# doodle_with_clock3_jump3.net
KiCad netlist of a schematic drawn in EAGLE
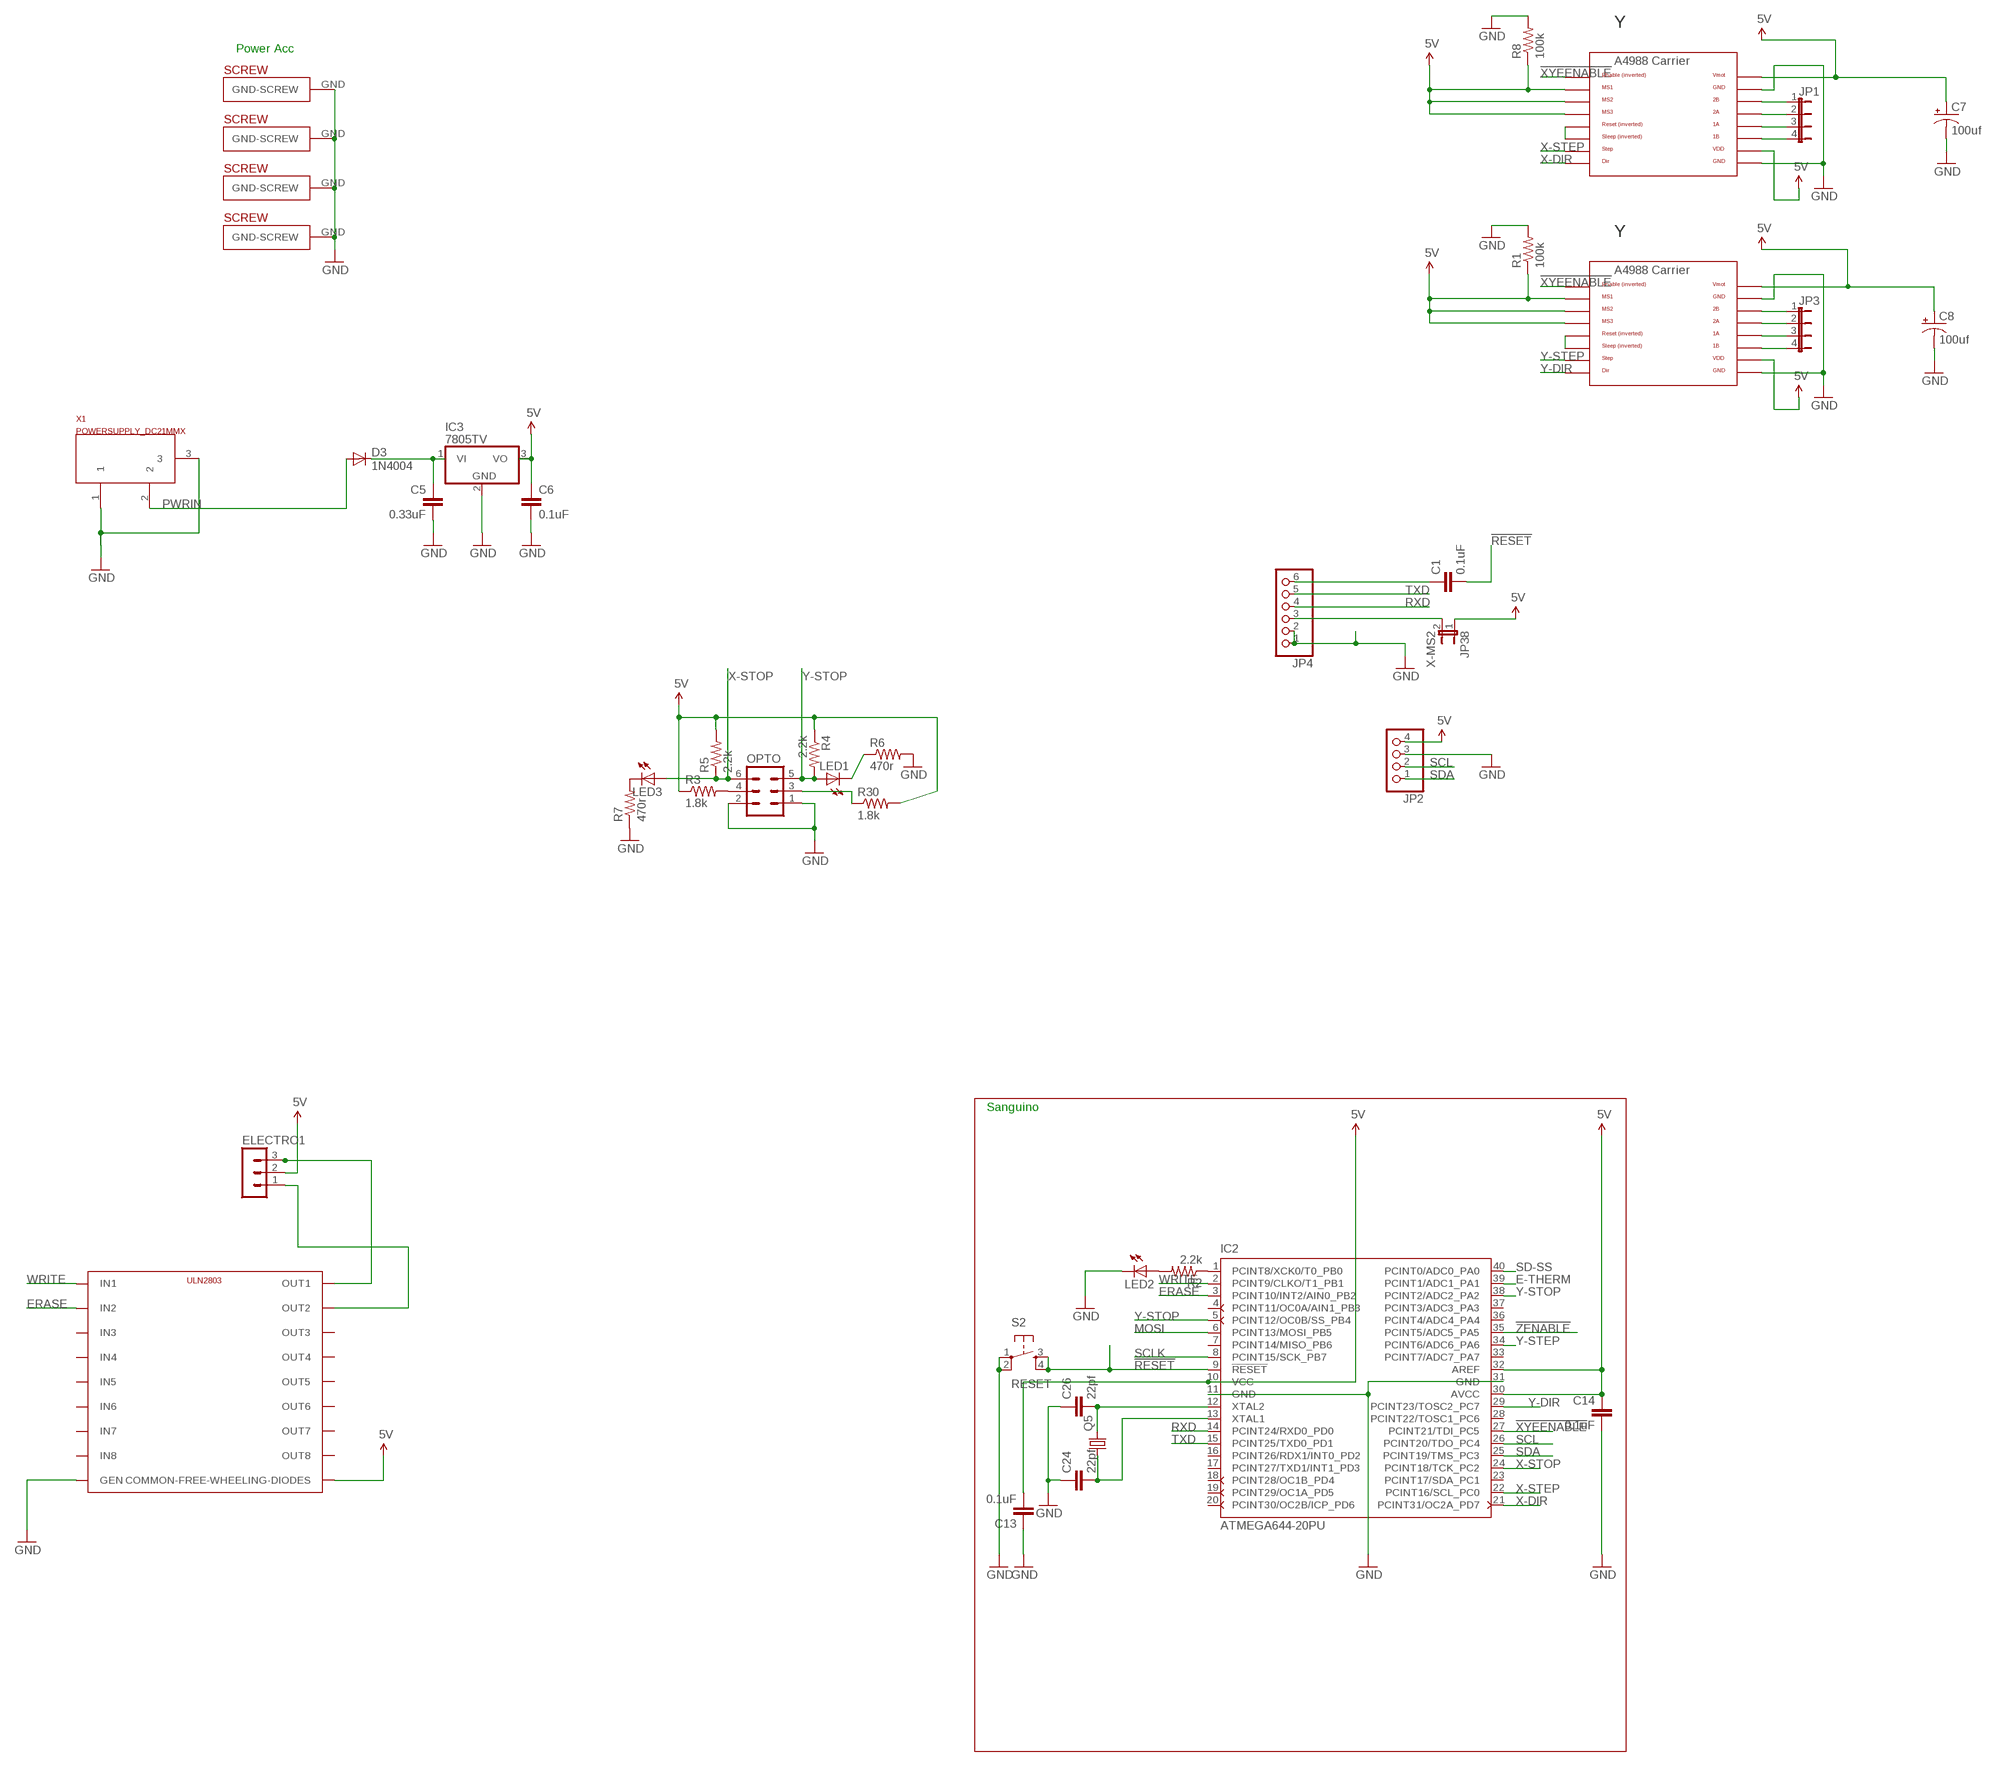
[diagram p0: schematic, sheet 1]

(export (version "E")
  (design (tool "Eeschema 10.0.6"))
  (components
    (comp (ref "C1")
      (value "0.1uF")
      (footprint "eagle-import:CAP-PTH-SMALL2")
      (libsource (lib "eagle-import") (part "CAPPTH2"))
    )
    (comp (ref "C5")
      (value "0.33uF")
      (footprint "eagle-import:CAP-PTH-SMALL2")
      (libsource (lib "eagle-import") (part "CAPPTH2"))
    )
    (comp (ref "C6")
      (value "0.1uF")
      (footprint "eagle-import:CAP-PTH-SMALL2")
      (libsource (lib "eagle-import") (part "CAPPTH2"))
    )
    (comp (ref "C7")
      (value "100uf")
      (footprint "eagle-import:CPOL-RADIAL-100UF-25V")
      (libsource (lib "eagle-import") (part "CAP_POLPTH1"))
    )
    (comp (ref "C8")
      (value "100uf")
      (footprint "eagle-import:CPOL-RADIAL-100UF-25V")
      (libsource (lib "eagle-import") (part "CAP_POLPTH1"))
    )
    (comp (ref "C13")
      (value "0.1uF")
      (footprint "eagle-import:CAP-PTH-SMALL2")
      (libsource (lib "eagle-import") (part "CAPPTH2"))
    )
    (comp (ref "C14")
      (value "0.1uF")
      (footprint "eagle-import:CAP-PTH-SMALL2")
      (libsource (lib "eagle-import") (part "CAPPTH2"))
    )
    (comp (ref "C24")
      (value "22pf")
      (footprint "eagle-import:CAP-PTH-SMALL2")
      (libsource (lib "eagle-import") (part "CAPPTH2"))
    )
    (comp (ref "C26")
      (value "22pf")
      (footprint "eagle-import:CAP-PTH-SMALL2")
      (libsource (lib "eagle-import") (part "CAPPTH2"))
    )
    (comp (ref "D3")
      (value "1N4004")
      (footprint "eagle-import:DO41-10")
      (libsource (lib "eagle-import") (part "1N4004"))
    )
    (comp (ref "ELECTRO1")
      (value "MA03-1")
      (footprint "eagle-import:MA03-1")
      (libsource (lib "eagle-import") (part "MA03-1"))
    )
    (comp (ref "IC2")
      (value "ATMEGA644-20PU")
      (footprint "eagle-import:DIL40")
      (libsource (lib "eagle-import") (part "ATMEGA644-PU20"))
    )
    (comp (ref "IC3")
      (value "7805TV")
      (footprint "eagle-import:TO220V")
      (libsource (lib "eagle-import") (part "78TV05"))
    )
    (comp (ref "JP1")
      (value "JP4E")
      (footprint "eagle-import:JP4")
      (libsource (lib "eagle-import") (part "JP4E"))
    )
    (comp (ref "JP2")
      (value "PINHD-1X4")
      (footprint "eagle-import:1X04")
      (libsource (lib "eagle-import") (part "PINHD-1X4"))
    )
    (comp (ref "JP3")
      (value "JP4E")
      (footprint "eagle-import:JP4")
      (libsource (lib "eagle-import") (part "JP4E"))
    )
    (comp (ref "JP4")
      (value "PINHD-1X6/90")
      (footprint "eagle-import:1X06_90")
      (libsource (lib "eagle-import") (part "PINHD-1X6/90"))
    )
    (comp (ref "JP38")
      (value "X-MS2")
      (footprint "eagle-import:1X02")
      (libsource (lib "eagle-import") (part "JUMPER-2PTH"))
    )
    (comp (ref "LED1")
      (value "LED3MM")
      (footprint "eagle-import:LED3MM")
      (libsource (lib "eagle-import") (part "LED3MM"))
    )
    (comp (ref "LED2")
      (value "LED3MM")
      (footprint "eagle-import:LED3MM")
      (libsource (lib "eagle-import") (part "LED3MM"))
    )
    (comp (ref "LED3")
      (value "LED3MM")
      (footprint "eagle-import:LED3MM")
      (libsource (lib "eagle-import") (part "LED3MM"))
    )
    (comp (ref "OPTO")
      (value "MA03-2")
      (footprint "eagle-import:MA03-2")
      (libsource (lib "eagle-import") (part "MA03-2"))
    )
    (comp (ref "Q5")
      (value "CRYSTALHC49S")
      (footprint "eagle-import:HC49_S")
      (libsource (lib "eagle-import") (part "CRYSTALHC49S"))
    )
    (comp (ref "R1")
      (value "100k")
      (footprint "eagle-import:0207_7")
      (libsource (lib "eagle-import") (part "R-US_0207/7"))
    )
    (comp (ref "R2")
      (value "2.2k")
      (footprint "eagle-import:0207_2V")
      (libsource (lib "eagle-import") (part "resistor_R-US_0207/2V"))
    )
    (comp (ref "R3")
      (value "1.8k")
      (footprint "eagle-import:0207_2V")
      (libsource (lib "eagle-import") (part "resistor_R-US_0207/2V"))
    )
    (comp (ref "R4")
      (value "2.2k")
      (footprint "eagle-import:0207_2V")
      (libsource (lib "eagle-import") (part "resistor_R-US_0207/2V"))
    )
    (comp (ref "R5")
      (value "2.2k")
      (footprint "eagle-import:0207_2V")
      (libsource (lib "eagle-import") (part "resistor_R-US_0207/2V"))
    )
    (comp (ref "R6")
      (value "470r")
      (footprint "eagle-import:0207_2V")
      (libsource (lib "eagle-import") (part "resistor_R-US_0207/2V"))
    )
    (comp (ref "R7")
      (value "470r")
      (footprint "eagle-import:0207_2V")
      (libsource (lib "eagle-import") (part "resistor_R-US_0207/2V"))
    )
    (comp (ref "R8")
      (value "100k")
      (footprint "eagle-import:0207_7")
      (libsource (lib "eagle-import") (part "R-US_0207/7"))
    )
    (comp (ref "R30")
      (value "1.8k")
      (footprint "eagle-import:0207_2V")
      (libsource (lib "eagle-import") (part "resistor_R-US_0207/2V"))
    )
    (comp (ref "S2")
      (value "RESET")
      (footprint "eagle-import:TACTILE-PTH")
      (libsource (lib "eagle-import") (part "TAC_SWITCHPTH"))
    )
    (comp (ref "U$1")
      (value "A4988BREAKOUT")
      (footprint "eagle-import:A4988BREAKOUT")
      (libsource (lib "eagle-import") (part "A4988BREAKOUT"))
    )
    (comp (ref "U$2")
      (value "ULN2803")
      (footprint "eagle-import:P-DIP")
      (libsource (lib "eagle-import") (part "ULN2803"))
    )
    (comp (ref "U$7")
      (value "A4988BREAKOUT")
      (footprint "eagle-import:A4988BREAKOUT")
      (libsource (lib "eagle-import") (part "A4988BREAKOUT"))
    )
    (comp (ref "U$14")
      (value "PLATED-SCREW")
      (footprint "eagle-import:PLATEDSCREW")
      (libsource (lib "eagle-import") (part "PLATED-SCREW"))
    )
    (comp (ref "U$17")
      (value "PLATED-SCREW")
      (footprint "eagle-import:PLATEDSCREW")
      (libsource (lib "eagle-import") (part "PLATED-SCREW"))
    )
    (comp (ref "U$18")
      (value "PLATED-SCREW")
      (footprint "eagle-import:PLATEDSCREW")
      (libsource (lib "eagle-import") (part "PLATED-SCREW"))
    )
    (comp (ref "U$38")
      (value "PLATED-SCREW")
      (footprint "eagle-import:PLATEDSCREW")
      (libsource (lib "eagle-import") (part "PLATED-SCREW"))
    )
    (comp (ref "X1")
      (value "POWERSUPPLY_DC21MMX")
      (footprint "eagle-import:POWERSUPPLY_DC-21MM")
      (libsource (lib "eagle-import") (part "POWERSUPPLY_DC21MMX"))
    )
  )
  (nets
    (net (code "1") (name "/E-THERM") (class "Default")
      (node (ref "IC2") (pin "39") (pinfunction "PCINT1/ADC1_PA1_39") (pintype "bidirectional"))
    )
    (net (code "2") (name "/ERASE") (class "Default")
      (node (ref "IC2") (pin "3") (pinfunction "PCINT10/INT2/AIN0_PB2_3") (pintype "bidirectional"))
      (node (ref "U$2") (pin "IN2") (pinfunction "IN2_IN2") (pintype "input"))
    )
    (net (code "3") (name "/MOSI") (class "Default")
      (node (ref "IC2") (pin "6") (pinfunction "PCINT13/MOSI_PB5_6") (pintype "bidirectional"))
    )
    (net (code "4") (name "/PWRIN") (class "Default")
      (node (ref "D3") (pin "A") (pinfunction "A_A") (pintype "passive"))
      (node (ref "X1") (pin "2") (pinfunction "2_2") (pintype "power_in"))
    )
    (net (code "5") (name "/RXD") (class "Default")
      (node (ref "IC2") (pin "14") (pinfunction "PCINT24/RXD0_PD0_14") (pintype "bidirectional"))
      (node (ref "JP4") (pin "4") (pinfunction "4_4") (pintype "passive"))
    )
    (net (code "6") (name "/SCL") (class "Default")
      (node (ref "IC2") (pin "26") (pinfunction "PCINT20/TDO_PC4_26") (pintype "bidirectional"))
      (node (ref "JP2") (pin "2") (pinfunction "2_2") (pintype "passive"))
    )
    (net (code "7") (name "/SCLK") (class "Default")
      (node (ref "IC2") (pin "8") (pinfunction "PCINT15/SCK_PB7_8") (pintype "bidirectional"))
    )
    (net (code "8") (name "/SD-SS") (class "Default")
      (node (ref "IC2") (pin "40") (pinfunction "PCINT0/ADC0_PA0_40") (pintype "bidirectional"))
    )
    (net (code "9") (name "/SDA") (class "Default")
      (node (ref "IC2") (pin "25") (pinfunction "PCINT19/TMS_PC3_25") (pintype "bidirectional"))
      (node (ref "JP2") (pin "1") (pinfunction "1_1") (pintype "passive"))
    )
    (net (code "10") (name "/TXD") (class "Default")
      (node (ref "IC2") (pin "15") (pinfunction "PCINT25/TXD0_PD1_15") (pintype "bidirectional"))
      (node (ref "JP4") (pin "5") (pinfunction "5_5") (pintype "passive"))
    )
    (net (code "11") (name "/WRITE") (class "Default")
      (node (ref "IC2") (pin "2") (pinfunction "PCINT9/CLKO/T1_PB1_2") (pintype "bidirectional"))
      (node (ref "U$2") (pin "IN1") (pinfunction "IN1_IN1") (pintype "input"))
    )
    (net (code "12") (name "/X-DIR") (class "Default")
      (node (ref "IC2") (pin "21") (pinfunction "PCINT31/OC2A_PD7_21") (pintype "bidirectional"))
      (node (ref "U$7") (pin "DIR") (pinfunction "DIR_DIR") (pintype "input"))
    )
    (net (code "13") (name "/X-STEP") (class "Default")
      (node (ref "IC2") (pin "22") (pinfunction "PCINT16/SCL_PC0_22") (pintype "bidirectional"))
      (node (ref "U$7") (pin "STEP") (pinfunction "STEP_STEP") (pintype "input"))
    )
    (net (code "14") (name "/X-STOP") (class "Default")
      (node (ref "IC2") (pin "24") (pinfunction "PCINT18/TCK_PC2_24") (pintype "bidirectional"))
      (node (ref "LED3") (pin "A") (pinfunction "A_A") (pintype "passive"))
      (node (ref "OPTO") (pin "6") (pinfunction "6_6") (pintype "passive"))
      (node (ref "R5") (pin "1") (pinfunction "1_1") (pintype "passive"))
    )
    (net (code "15") (name "/Y-DIR") (class "Default")
      (node (ref "IC2") (pin "29") (pinfunction "PCINT23/TOSC2_PC7_29") (pintype "bidirectional"))
      (node (ref "U$1") (pin "DIR") (pinfunction "DIR_DIR") (pintype "input"))
    )
    (net (code "16") (name "/Y-STEP") (class "Default")
      (node (ref "IC2") (pin "34") (pinfunction "PCINT6/ADC6_PA6_34") (pintype "bidirectional"))
      (node (ref "U$1") (pin "STEP") (pinfunction "STEP_STEP") (pintype "input"))
    )
    (net (code "17") (name "/Y-STOP") (class "Default")
      (node (ref "IC2") (pin "38") (pinfunction "PCINT2/ADC2_PA2_38") (pintype "bidirectional"))
      (node (ref "IC2") (pin "5") (pinfunction "PCINT12/OC0B/SS_PB4_5") (pintype "bidirectional"))
      (node (ref "LED1") (pin "A") (pinfunction "A_A") (pintype "passive"))
      (node (ref "OPTO") (pin "5") (pinfunction "5_5") (pintype "passive"))
      (node (ref "R4") (pin "2") (pinfunction "2_2") (pintype "passive"))
    )
    (net (code "18") (name "/~{RESET}") (class "Default")
      (node (ref "C1") (pin "2") (pinfunction "2_2") (pintype "passive"))
      (node (ref "IC2") (pin "9") (pinfunction "~{RESET}_9") (pintype "input"))
      (node (ref "S2") (pin "3") (pinfunction "3_3") (pintype "passive"))
      (node (ref "S2") (pin "4") (pinfunction "4_4") (pintype "passive"))
    )
    (net (code "19") (name "/~{XYEENABLE}") (class "Default")
      (node (ref "IC2") (pin "27") (pinfunction "PCINT21/TDI_PC5_27") (pintype "bidirectional"))
      (node (ref "U$1") (pin "EN") (pinfunction "EN_EN") (pintype "input"))
      (node (ref "U$7") (pin "EN") (pinfunction "EN_EN") (pintype "input"))
    )
    (net (code "20") (name "/~{ZENABLE}") (class "Default")
      (node (ref "IC2") (pin "35") (pinfunction "PCINT5/ADC5_PA5_35") (pintype "bidirectional"))
    )
    (net (code "21") (name "5V") (class "Default")
      (node (ref "C13") (pin "2") (pinfunction "2_2") (pintype "passive"))
      (node (ref "C14") (pin "1") (pinfunction "1_1") (pintype "passive"))
      (node (ref "C6") (pin "1") (pinfunction "1_1") (pintype "passive"))
      (node (ref "C7") (pin "1") (pinfunction "+_1") (pintype "passive"))
      (node (ref "C8") (pin "1") (pinfunction "+_1") (pintype "passive"))
      (node (ref "ELECTRO1") (pin "2") (pinfunction "2_2") (pintype "passive"))
      (node (ref "IC2") (pin "10") (pinfunction "VCC_10") (pintype "power_in"))
      (node (ref "IC2") (pin "30") (pinfunction "AVCC_30") (pintype "power_in"))
      (node (ref "IC2") (pin "32") (pinfunction "AREF_32") (pintype "passive"))
      (node (ref "IC3") (pin "3") (pinfunction "VO_3") (pintype "passive"))
      (node (ref "JP2") (pin "4") (pinfunction "4_4") (pintype "passive"))
      (node (ref "JP38") (pin "1") (pinfunction "1_1") (pintype "passive"))
      (node (ref "R1") (pin "1") (pinfunction "1_1") (pintype "passive"))
      (node (ref "R3") (pin "1") (pinfunction "1_1") (pintype "passive"))
      (node (ref "R30") (pin "2") (pinfunction "2_2") (pintype "passive"))
      (node (ref "R4") (pin "1") (pinfunction "1_1") (pintype "passive"))
      (node (ref "R5") (pin "2") (pinfunction "2_2") (pintype "passive"))
      (node (ref "R8") (pin "1") (pinfunction "1_1") (pintype "passive"))
      (node (ref "U$1") (pin "MS1") (pinfunction "MS1_MS1") (pintype "input"))
      (node (ref "U$1") (pin "MS2") (pinfunction "MS2_MS2") (pintype "input"))
      (node (ref "U$1") (pin "MS3") (pinfunction "MS3_MS3") (pintype "input"))
      (node (ref "U$1") (pin "VDD") (pinfunction "VDD_VDD") (pintype "power_in"))
      (node (ref "U$1") (pin "VMOT") (pinfunction "VMOT_VMOT") (pintype "power_in"))
      (node (ref "U$2") (pin "COMMON-FREE-WHEELING-DIODES") (pinfunction "COMMON-FREE-WHEELING-DIODES_COMMON-FREE-WHEELING-DIODES") (pintype "output"))
      (node (ref "U$7") (pin "MS1") (pinfunction "MS1_MS1") (pintype "input"))
      (node (ref "U$7") (pin "MS2") (pinfunction "MS2_MS2") (pintype "input"))
      (node (ref "U$7") (pin "MS3") (pinfunction "MS3_MS3") (pintype "input"))
      (node (ref "U$7") (pin "VDD") (pinfunction "VDD_VDD") (pintype "power_in"))
      (node (ref "U$7") (pin "VMOT") (pinfunction "VMOT_VMOT") (pintype "power_in"))
    )
    (net (code "22") (name "GND") (class "Default")
      (node (ref "C13") (pin "1") (pinfunction "1_1") (pintype "passive"))
      (node (ref "C14") (pin "2") (pinfunction "2_2") (pintype "passive"))
      (node (ref "C24") (pin "1") (pinfunction "1_1") (pintype "passive"))
      (node (ref "C26") (pin "1") (pinfunction "1_1") (pintype "passive"))
      (node (ref "C5") (pin "2") (pinfunction "2_2") (pintype "passive"))
      (node (ref "C6") (pin "2") (pinfunction "2_2") (pintype "passive"))
      (node (ref "C7") (pin "2") (pinfunction "-_2") (pintype "passive"))
      (node (ref "C8") (pin "2") (pinfunction "-_2") (pintype "passive"))
      (node (ref "IC2") (pin "11") (pinfunction "GND_11") (pintype "power_in"))
      (node (ref "IC2") (pin "31") (pinfunction "GND_31") (pintype "power_in"))
      (node (ref "IC3") (pin "2") (pinfunction "GND_2") (pintype "passive"))
      (node (ref "JP2") (pin "3") (pinfunction "3_3") (pintype "passive"))
      (node (ref "JP4") (pin "1") (pinfunction "1_1") (pintype "passive"))
      (node (ref "JP4") (pin "2") (pinfunction "2_2") (pintype "passive"))
      (node (ref "LED2") (pin "K") (pinfunction "C_K") (pintype "passive"))
      (node (ref "OPTO") (pin "1") (pinfunction "1_1") (pintype "passive"))
      (node (ref "OPTO") (pin "2") (pinfunction "2_2") (pintype "passive"))
      (node (ref "R1") (pin "2") (pinfunction "2_2") (pintype "passive"))
      (node (ref "R6") (pin "2") (pinfunction "2_2") (pintype "passive"))
      (node (ref "R7") (pin "1") (pinfunction "1_1") (pintype "passive"))
      (node (ref "R8") (pin "2") (pinfunction "2_2") (pintype "passive"))
      (node (ref "S2") (pin "1") (pinfunction "1_1") (pintype "passive"))
      (node (ref "S2") (pin "2") (pinfunction "2_2") (pintype "passive"))
      (node (ref "U$1") (pin "GND") (pinfunction "GND_GND") (pintype "power_in"))
      (node (ref "U$1") (pin "GND@0") (pinfunction "GND_GND@0") (pintype "power_in"))
      (node (ref "U$14") (pin "GND") (pinfunction "GND-SCREW_GND") (pintype "bidirectional"))
      (node (ref "U$17") (pin "GND") (pinfunction "GND-SCREW_GND") (pintype "bidirectional"))
      (node (ref "U$18") (pin "GND") (pinfunction "GND-SCREW_GND") (pintype "bidirectional"))
      (node (ref "U$2") (pin "GEN") (pinfunction "GEN_GEN") (pintype "power_in"))
      (node (ref "U$38") (pin "GND") (pinfunction "GND-SCREW_GND") (pintype "bidirectional"))
      (node (ref "U$7") (pin "GND") (pinfunction "GND_GND") (pintype "power_in"))
      (node (ref "U$7") (pin "GND@0") (pinfunction "GND_GND@0") (pintype "power_in"))
      (node (ref "X1") (pin "1") (pinfunction "1_1") (pintype "power_in"))
      (node (ref "X1") (pin "3") (pinfunction "3_3") (pintype "power_in"))
    )
    (net (code "23") (name "Net-(C1-Pad1)") (class "Default")
      (node (ref "C1") (pin "1") (pinfunction "1_1") (pintype "passive"))
      (node (ref "JP4") (pin "6") (pinfunction "6_6") (pintype "passive"))
    )
    (net (code "24") (name "Net-(ELECTRO1-Pad1)") (class "Default")
      (node (ref "ELECTRO1") (pin "1") (pinfunction "1_1") (pintype "passive"))
      (node (ref "U$2") (pin "OUT2") (pinfunction "OUT2_OUT2") (pintype "output"))
    )
    (net (code "25") (name "Net-(ELECTRO1-Pad3)") (class "Default")
      (node (ref "ELECTRO1") (pin "3") (pinfunction "3_3") (pintype "passive"))
      (node (ref "U$2") (pin "OUT1") (pinfunction "OUT1_OUT1") (pintype "output"))
    )
    (net (code "26") (name "Net-(IC2-PCINT8{slash}XCK0{slash}T0_PB0)") (class "Default")
      (node (ref "IC2") (pin "1") (pinfunction "PCINT8/XCK0/T0_PB0_1") (pintype "bidirectional"))
      (node (ref "R2") (pin "1") (pinfunction "1_1") (pintype "passive"))
    )
    (net (code "27") (name "Net-(IC2-XTAL1)") (class "Default")
      (node (ref "C24") (pin "2") (pinfunction "2_2") (pintype "passive"))
      (node (ref "IC2") (pin "13") (pinfunction "XTAL1_13") (pintype "input"))
      (node (ref "Q5") (pin "1") (pinfunction "1_1") (pintype "passive"))
    )
    (net (code "28") (name "Net-(IC2-XTAL2)") (class "Default")
      (node (ref "C26") (pin "2") (pinfunction "2_2") (pintype "passive"))
      (node (ref "IC2") (pin "12") (pinfunction "XTAL2_12") (pintype "output"))
      (node (ref "Q5") (pin "2") (pinfunction "2_2") (pintype "passive"))
    )
    (net (code "29") (name "Net-(IC3-VI)") (class "Default")
      (node (ref "C5") (pin "1") (pinfunction "1_1") (pintype "passive"))
      (node (ref "D3") (pin "C") (pinfunction "C_C") (pintype "passive"))
      (node (ref "IC3") (pin "1") (pinfunction "VI_1") (pintype "input"))
    )
    (net (code "30") (name "Net-(JP1-Pad1)") (class "Default")
      (node (ref "JP1") (pin "1") (pinfunction "1_1") (pintype "passive"))
      (node (ref "U$7") (pin "2B") (pinfunction "2B_2B") (pintype "output"))
    )
    (net (code "31") (name "Net-(JP1-Pad2)") (class "Default")
      (node (ref "JP1") (pin "2") (pinfunction "2_2") (pintype "passive"))
      (node (ref "U$7") (pin "2A") (pinfunction "2A_2A") (pintype "output"))
    )
    (net (code "32") (name "Net-(JP1-Pad3)") (class "Default")
      (node (ref "JP1") (pin "3") (pinfunction "3_3") (pintype "passive"))
      (node (ref "U$7") (pin "1A") (pinfunction "1A_1A") (pintype "output"))
    )
    (net (code "33") (name "Net-(JP1-Pad4)") (class "Default")
      (node (ref "JP1") (pin "4") (pinfunction "4_4") (pintype "passive"))
      (node (ref "U$7") (pin "1B") (pinfunction "1B_1B") (pintype "output"))
    )
    (net (code "34") (name "Net-(JP3-Pad1)") (class "Default")
      (node (ref "JP3") (pin "1") (pinfunction "1_1") (pintype "passive"))
      (node (ref "U$1") (pin "2B") (pinfunction "2B_2B") (pintype "output"))
    )
    (net (code "35") (name "Net-(JP3-Pad2)") (class "Default")
      (node (ref "JP3") (pin "2") (pinfunction "2_2") (pintype "passive"))
      (node (ref "U$1") (pin "2A") (pinfunction "2A_2A") (pintype "output"))
    )
    (net (code "36") (name "Net-(JP3-Pad3)") (class "Default")
      (node (ref "JP3") (pin "3") (pinfunction "3_3") (pintype "passive"))
      (node (ref "U$1") (pin "1A") (pinfunction "1A_1A") (pintype "output"))
    )
    (net (code "37") (name "Net-(JP3-Pad4)") (class "Default")
      (node (ref "JP3") (pin "4") (pinfunction "4_4") (pintype "passive"))
      (node (ref "U$1") (pin "1B") (pinfunction "1B_1B") (pintype "output"))
    )
    (net (code "38") (name "Net-(JP38-Pad2)") (class "Default")
      (node (ref "JP38") (pin "2") (pinfunction "2_2") (pintype "passive"))
      (node (ref "JP4") (pin "3") (pinfunction "3_3") (pintype "passive"))
    )
    (net (code "39") (name "Net-(LED1-C)") (class "Default")
      (node (ref "LED1") (pin "K") (pinfunction "C_K") (pintype "passive"))
      (node (ref "R6") (pin "1") (pinfunction "1_1") (pintype "passive"))
    )
    (net (code "40") (name "Net-(LED2-PadA)") (class "Default")
      (node (ref "LED2") (pin "A") (pinfunction "A_A") (pintype "passive"))
      (node (ref "R2") (pin "2") (pinfunction "2_2") (pintype "passive"))
    )
    (net (code "41") (name "Net-(LED3-C)") (class "Default")
      (node (ref "LED3") (pin "K") (pinfunction "C_K") (pintype "passive"))
      (node (ref "R7") (pin "2") (pinfunction "2_2") (pintype "passive"))
    )
    (net (code "42") (name "Net-(OPTO-Pad3)") (class "Default")
      (node (ref "OPTO") (pin "3") (pinfunction "3_3") (pintype "passive"))
      (node (ref "R30") (pin "1") (pinfunction "1_1") (pintype "passive"))
    )
    (net (code "43") (name "Net-(OPTO-Pad4)") (class "Default")
      (node (ref "OPTO") (pin "4") (pinfunction "4_4") (pintype "passive"))
      (node (ref "R3") (pin "2") (pinfunction "2_2") (pintype "passive"))
    )
    (net (code "44") (name "Net-(U$1-SLEEP)") (class "Default")
      (node (ref "U$1") (pin "RST") (pinfunction "RST_RST") (pintype "input"))
      (node (ref "U$1") (pin "SLP") (pinfunction "SLEEP_SLP") (pintype "input"))
    )
    (net (code "45") (name "Net-(U$7-SLEEP)") (class "Default")
      (node (ref "U$7") (pin "RST") (pinfunction "RST_RST") (pintype "input"))
      (node (ref "U$7") (pin "SLP") (pinfunction "SLEEP_SLP") (pintype "input"))
    )
    (net (code "46") (name "unconnected-(IC2-PCINT3{slash}ADC3_PA3-Pad37)") (class "Default")
      (node (ref "IC2") (pin "37") (pinfunction "PCINT3/ADC3_PA3_37") (pintype "bidirectional"))
    )
    (net (code "47") (name "unconnected-(IC2-PCINT4{slash}ADC4_PA4-Pad36)") (class "Default")
      (node (ref "IC2") (pin "36") (pinfunction "PCINT4/ADC4_PA4_36") (pintype "bidirectional"))
    )
    (net (code "48") (name "unconnected-(IC2-PCINT7{slash}ADC7_PA7-Pad33)") (class "Default")
      (node (ref "IC2") (pin "33") (pinfunction "PCINT7/ADC7_PA7_33") (pintype "bidirectional"))
    )
    (net (code "49") (name "unconnected-(IC2-PCINT11{slash}OC0A{slash}AIN1_PB3-Pad4)") (class "Default")
      (node (ref "IC2") (pin "4") (pinfunction "PCINT11/OC0A/AIN1_PB3_4") (pintype "bidirectional"))
    )
    (net (code "50") (name "unconnected-(IC2-PCINT14{slash}MISO_PB6-Pad7)") (class "Default")
      (node (ref "IC2") (pin "7") (pinfunction "PCINT14/MISO_PB6_7") (pintype "bidirectional"))
    )
    (net (code "51") (name "unconnected-(IC2-PCINT17{slash}SDA_PC1-Pad23)") (class "Default")
      (node (ref "IC2") (pin "23") (pinfunction "PCINT17/SDA_PC1_23") (pintype "bidirectional"))
    )
    (net (code "52") (name "unconnected-(IC2-PCINT22{slash}TOSC1_PC6-Pad28)") (class "Default")
      (node (ref "IC2") (pin "28") (pinfunction "PCINT22/TOSC1_PC6_28") (pintype "bidirectional"))
    )
    (net (code "53") (name "unconnected-(IC2-PCINT26{slash}RDX1{slash}INT0_PD2-Pad16)") (class "Default")
      (node (ref "IC2") (pin "16") (pinfunction "PCINT26/RDX1/INT0_PD2_16") (pintype "bidirectional"))
    )
    (net (code "54") (name "unconnected-(IC2-PCINT27{slash}TXD1{slash}INT1_PD3-Pad17)") (class "Default")
      (node (ref "IC2") (pin "17") (pinfunction "PCINT27/TXD1/INT1_PD3_17") (pintype "bidirectional"))
    )
    (net (code "55") (name "unconnected-(IC2-PCINT28{slash}OC1B_PD4-Pad18)") (class "Default")
      (node (ref "IC2") (pin "18") (pinfunction "PCINT28/OC1B_PD4_18") (pintype "bidirectional"))
    )
    (net (code "56") (name "unconnected-(IC2-PCINT29{slash}OC1A_PD5-Pad19)") (class "Default")
      (node (ref "IC2") (pin "19") (pinfunction "PCINT29/OC1A_PD5_19") (pintype "bidirectional"))
    )
    (net (code "57") (name "unconnected-(IC2-PCINT30{slash}OC2B{slash}ICP_PD6-Pad20)") (class "Default")
      (node (ref "IC2") (pin "20") (pinfunction "PCINT30/OC2B/ICP_PD6_20") (pintype "bidirectional"))
    )
    (net (code "58") (name "unconnected-(U$2-PadIN3)") (class "Default")
      (node (ref "U$2") (pin "IN3") (pinfunction "IN3_IN3") (pintype "input"))
    )
    (net (code "59") (name "unconnected-(U$2-PadIN4)") (class "Default")
      (node (ref "U$2") (pin "IN4") (pinfunction "IN4_IN4") (pintype "input"))
    )
    (net (code "60") (name "unconnected-(U$2-PadIN5)") (class "Default")
      (node (ref "U$2") (pin "IN5") (pinfunction "IN5_IN5") (pintype "input"))
    )
    (net (code "61") (name "unconnected-(U$2-PadIN6)") (class "Default")
      (node (ref "U$2") (pin "IN6") (pinfunction "IN6_IN6") (pintype "input"))
    )
    (net (code "62") (name "unconnected-(U$2-PadIN7)") (class "Default")
      (node (ref "U$2") (pin "IN7") (pinfunction "IN7_IN7") (pintype "input"))
    )
    (net (code "63") (name "unconnected-(U$2-PadIN8)") (class "Default")
      (node (ref "U$2") (pin "IN8") (pinfunction "IN8_IN8") (pintype "input"))
    )
    (net (code "64") (name "unconnected-(U$2-PadOUT3)") (class "Default")
      (node (ref "U$2") (pin "OUT3") (pinfunction "OUT3_OUT3") (pintype "output"))
    )
    (net (code "65") (name "unconnected-(U$2-PadOUT4)") (class "Default")
      (node (ref "U$2") (pin "OUT4") (pinfunction "OUT4_OUT4") (pintype "output"))
    )
    (net (code "66") (name "unconnected-(U$2-PadOUT5)") (class "Default")
      (node (ref "U$2") (pin "OUT5") (pinfunction "OUT5_OUT5") (pintype "output"))
    )
    (net (code "67") (name "unconnected-(U$2-PadOUT6)") (class "Default")
      (node (ref "U$2") (pin "OUT6") (pinfunction "OUT6_OUT6") (pintype "output"))
    )
    (net (code "68") (name "unconnected-(U$2-PadOUT7)") (class "Default")
      (node (ref "U$2") (pin "OUT7") (pinfunction "OUT7_OUT7") (pintype "output"))
    )
    (net (code "69") (name "unconnected-(U$2-PadOUT8)") (class "Default")
      (node (ref "U$2") (pin "OUT8") (pinfunction "OUT8_OUT8") (pintype "output"))
    )
  )
)
